# wisleep.net
KiCad netlist of a schematic drawn in EAGLE
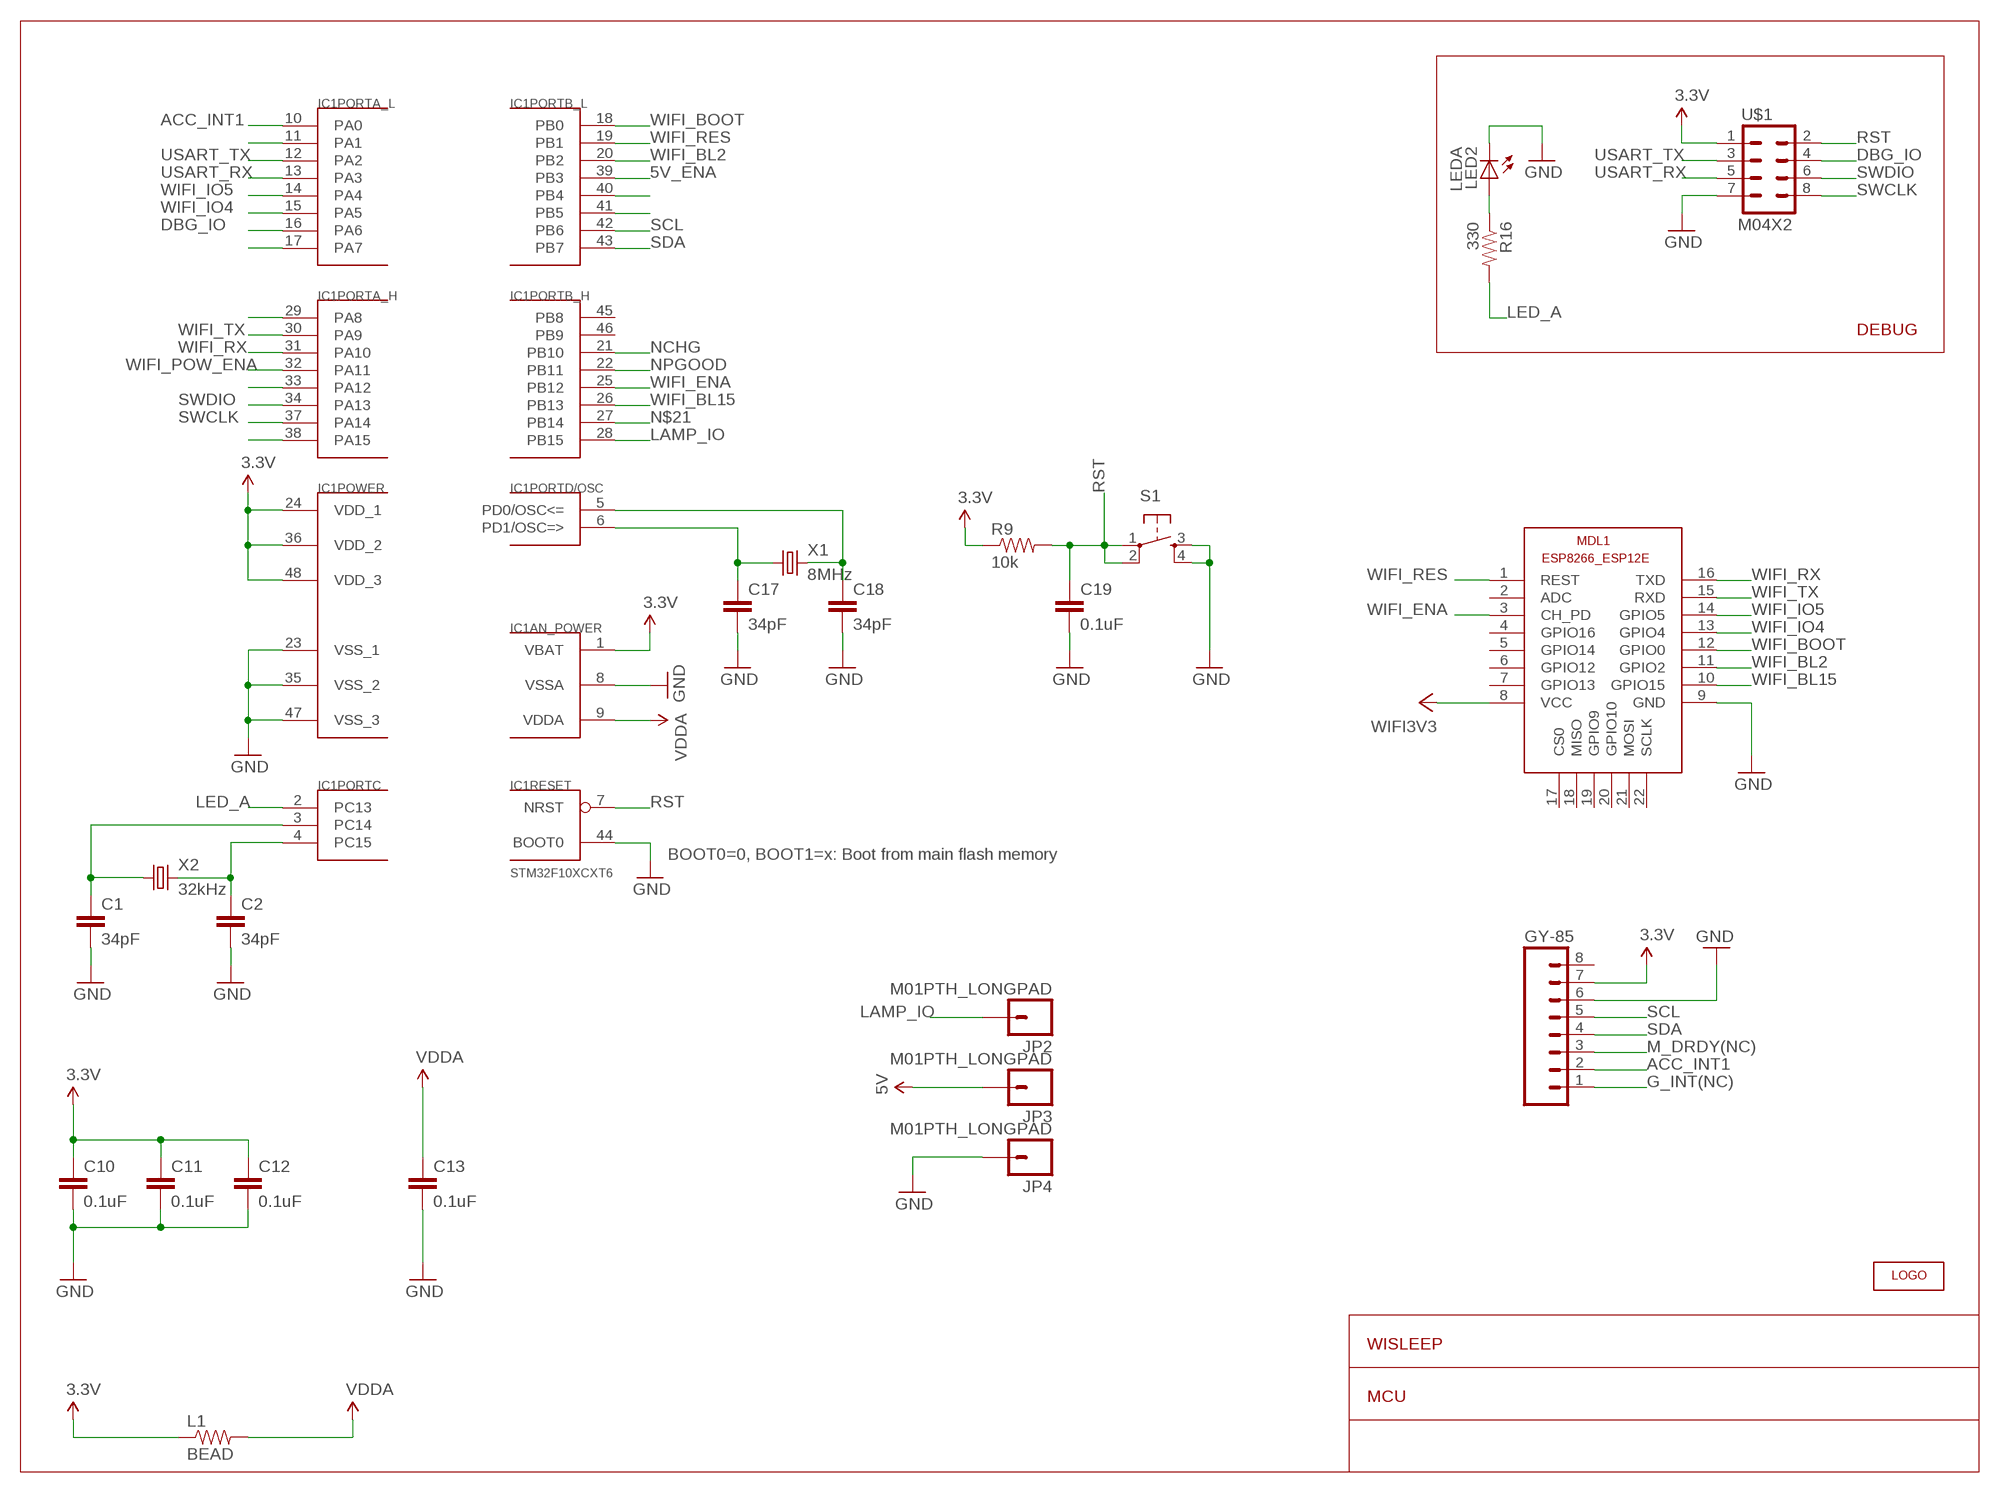
[diagram p0: schematic, sheet 1]
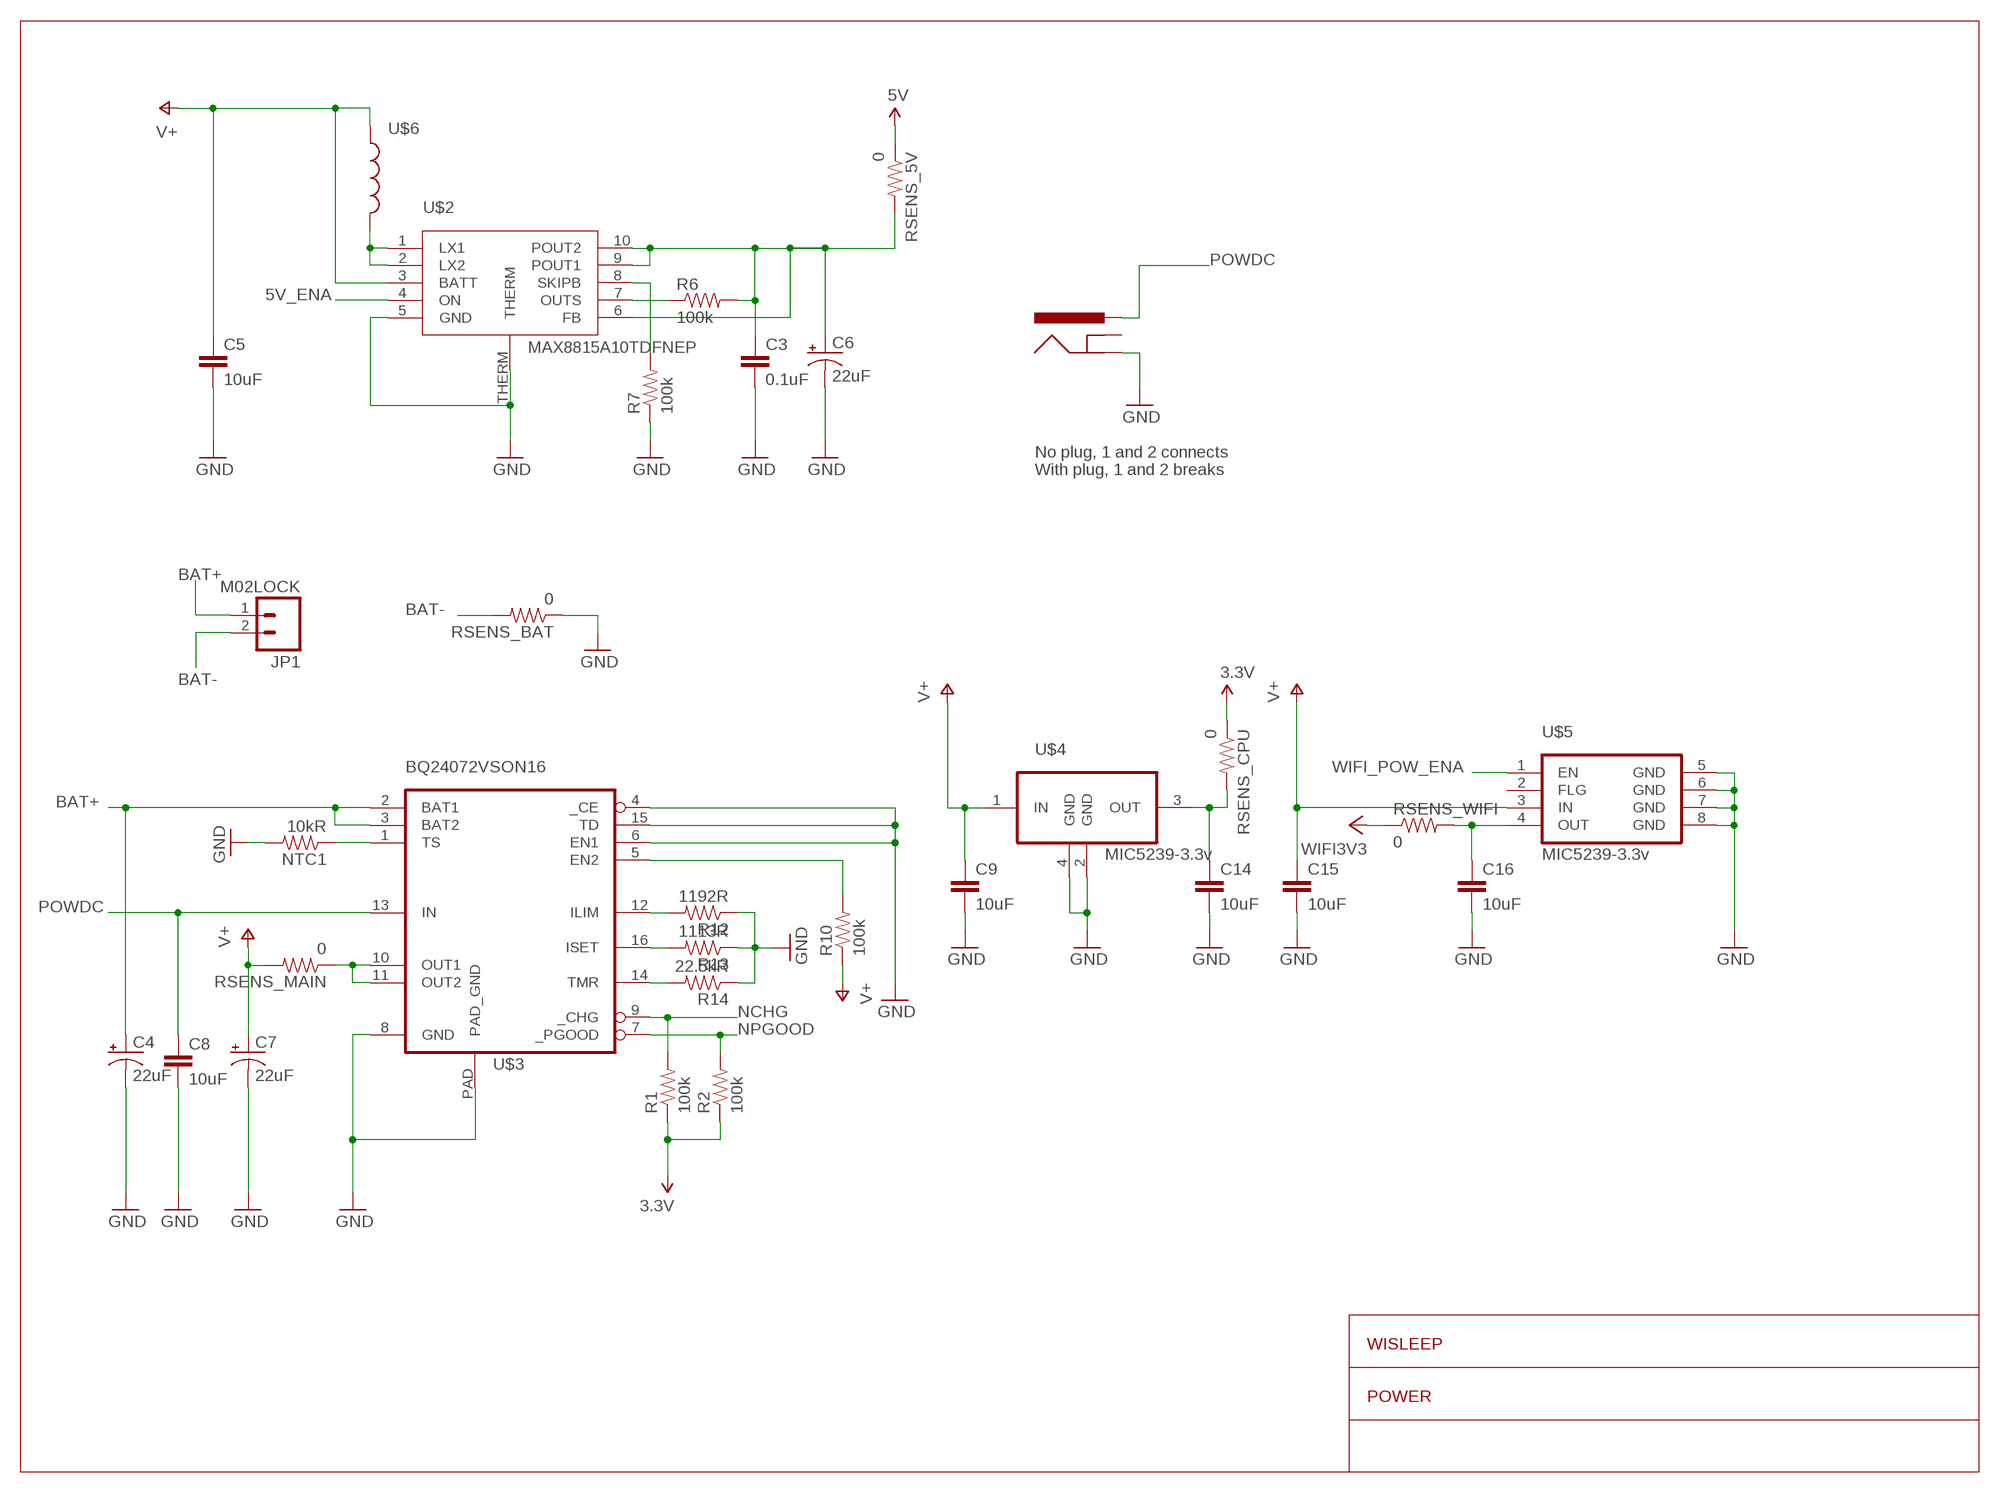
[diagram p1: schematic, sheet 2]

(export (version "E")
  (design (tool "Eeschema 10.0.6"))
  (components
    (comp (ref "C1")
      (value "34pF")
      (footprint "eagle-import:C0402")
      (libsource (lib "eagle-import") (part "CAP0402"))
    )
    (comp (ref "C2")
      (value "34pF")
      (footprint "eagle-import:C0402")
      (libsource (lib "eagle-import") (part "CAP0402"))
    )
    (comp (ref "C10")
      (value "0.1uF")
      (footprint "eagle-import:C0402")
      (libsource (lib "eagle-import") (part "CAP0402"))
    )
    (comp (ref "C11")
      (value "0.1uF")
      (footprint "eagle-import:C0402")
      (libsource (lib "eagle-import") (part "CAP0402"))
    )
    (comp (ref "C12")
      (value "0.1uF")
      (footprint "eagle-import:C0402")
      (libsource (lib "eagle-import") (part "CAP0402"))
    )
    (comp (ref "C13")
      (value "0.1uF")
      (footprint "eagle-import:C0402")
      (libsource (lib "eagle-import") (part "CAP0402"))
    )
    (comp (ref "C17")
      (value "34pF")
      (footprint "eagle-import:C0402")
      (libsource (lib "eagle-import") (part "CAP0402"))
    )
    (comp (ref "C18")
      (value "34pF")
      (footprint "eagle-import:C0402")
      (libsource (lib "eagle-import") (part "CAP0402"))
    )
    (comp (ref "C19")
      (value "0.1uF")
      (footprint "eagle-import:C0402")
      (libsource (lib "eagle-import") (part "CAP0402"))
    )
    (comp (ref "GY-85")
      (value "M08")
      (footprint "eagle-import:1X08")
      (libsource (lib "eagle-import") (part "M08"))
    )
    (comp (ref "IC1")
      (value "STM32F10XCXT6")
      (footprint "eagle-import:TQFP48")
      (libsource (lib "eagle-import") (part "STM32F10XCXT6"))
    )
    (comp (ref "JP2")
      (value "M01PTH_LONGPAD")
      (footprint "eagle-import:1X01_LONGPAD")
      (libsource (lib "eagle-import") (part "M01PTH_LONGPAD"))
    )
    (comp (ref "JP3")
      (value "M01PTH_LONGPAD")
      (footprint "eagle-import:1X01_LONGPAD")
      (libsource (lib "eagle-import") (part "M01PTH_LONGPAD"))
    )
    (comp (ref "JP4")
      (value "M01PTH_LONGPAD")
      (footprint "eagle-import:1X01_LONGPAD")
      (libsource (lib "eagle-import") (part "M01PTH_LONGPAD"))
    )
    (comp (ref "L1")
      (value "BEAD")
      (footprint "eagle-import:0603_GEN")
      (libsource (lib "eagle-import") (part "robot_RESISTOR0603"))
    )
    (comp (ref "LED2")
      (value "LEDA")
      (footprint "eagle-import:LED-0603")
      (libsource (lib "eagle-import") (part "LED0603"))
    )
    (comp (ref "MDL1")
      (value "ESP8266-12EESP8266-ESP12E")
      (footprint "eagle-import:ESP8266-ESP12E")
      (libsource (lib "eagle-import") (part "ESP8266-12EESP8266-ESP12E"))
    )
    (comp (ref "R9")
      (value "10k")
      (footprint "eagle-import:C0402")
      (libsource (lib "eagle-import") (part "RESISTOR0402"))
    )
    (comp (ref "R16")
      (value "330")
      (footprint "eagle-import:C0402")
      (libsource (lib "eagle-import") (part "RESISTOR0402"))
    )
    (comp (ref "S1")
      (value "TAC_SWITCHSMD")
      (footprint "eagle-import:TACTILE_SWITCH_SMD")
      (libsource (lib "eagle-import") (part "TAC_SWITCHSMD"))
    )
    (comp (ref "U$1")
      (value "M04X2")
      (footprint "eagle-import:2X4")
      (libsource (lib "eagle-import") (part "M04X2"))
    )
    (comp (ref "U$7")
      (value "LOGOLOGO")
      (footprint "eagle-import:LOGO")
      (libsource (lib "eagle-import") (part "LOGOLOGO"))
    )
    (comp (ref "X1")
      (value "8MHz")
      (footprint "eagle-import:CRYSTAL_SMD_5X3.2_7A")
      (libsource (lib "eagle-import") (part "CRYSTAL5X3.2_7AOWN"))
    )
    (comp (ref "X2")
      (value "32kHz")
      (footprint "eagle-import:CRYSTAL_SMD_2X0.6")
      (libsource (lib "eagle-import") (part "CRYSTAL"))
    )
    (comp (ref "C3")
      (value "0.1uF")
      (footprint "eagle-import:C0402")
      (libsource (lib "eagle-import") (part "CAP0402"))
    )
    (comp (ref "C4")
      (value "22uF")
      (footprint "eagle-import:EIA3216")
      (libsource (lib "eagle-import") (part "CAP_POL1206_CASE-A"))
    )
    (comp (ref "C5")
      (value "10uF")
      (footprint "eagle-import:C0402")
      (libsource (lib "eagle-import") (part "CAP0402"))
    )
    (comp (ref "C6")
      (value "22uF")
      (footprint "eagle-import:EIA3216")
      (libsource (lib "eagle-import") (part "CAP_POL1206_CASE-A"))
    )
    (comp (ref "C7")
      (value "22uF")
      (footprint "eagle-import:EIA3216")
      (libsource (lib "eagle-import") (part "CAP_POL1206_CASE-A"))
    )
    (comp (ref "C8")
      (value "10uF")
      (footprint "eagle-import:C0402")
      (libsource (lib "eagle-import") (part "CAP0402"))
    )
    (comp (ref "C9")
      (value "10uF")
      (footprint "eagle-import:C0402")
      (libsource (lib "eagle-import") (part "CAP0402"))
    )
    (comp (ref "C14")
      (value "10uF")
      (footprint "eagle-import:C0402")
      (libsource (lib "eagle-import") (part "CAP0402"))
    )
    (comp (ref "C15")
      (value "10uF")
      (footprint "eagle-import:C0402")
      (libsource (lib "eagle-import") (part "CAP0402"))
    )
    (comp (ref "C16")
      (value "10uF")
      (footprint "eagle-import:C0402")
      (libsource (lib "eagle-import") (part "CAP0402"))
    )
    (comp (ref "JP1")
      (value "M02LOCK")
      (footprint "eagle-import:1X02_LOCK")
      (libsource (lib "eagle-import") (part "M02LOCK"))
    )
    (comp (ref "NTC1")
      (value "10kR")
      (footprint "eagle-import:C0402")
      (libsource (lib "eagle-import") (part "RESISTOR0402"))
    )
    (comp (ref "R1")
      (value "100k")
      (footprint "eagle-import:C0402")
      (libsource (lib "eagle-import") (part "RESISTOR0402"))
    )
    (comp (ref "R2")
      (value "100k")
      (footprint "eagle-import:C0402")
      (libsource (lib "eagle-import") (part "RESISTOR0402"))
    )
    (comp (ref "R6")
      (value "100k")
      (footprint "eagle-import:C0402")
      (libsource (lib "eagle-import") (part "RESISTOR0402"))
    )
    (comp (ref "R7")
      (value "100k")
      (footprint "eagle-import:C0402")
      (libsource (lib "eagle-import") (part "RESISTOR0402"))
    )
    (comp (ref "R10")
      (value "100k")
      (footprint "eagle-import:C0402")
      (libsource (lib "eagle-import") (part "RESISTOR0402"))
    )
    (comp (ref "R12")
      (value "1192R")
      (footprint "eagle-import:C0402")
      (libsource (lib "eagle-import") (part "RESISTOR0402"))
    )
    (comp (ref "R13")
      (value "1113R")
      (footprint "eagle-import:C0402")
      (libsource (lib "eagle-import") (part "RESISTOR0402"))
    )
    (comp (ref "R14")
      (value "22.5kR")
      (footprint "eagle-import:C0402")
      (libsource (lib "eagle-import") (part "RESISTOR0402"))
    )
    (comp (ref "RSENS_5V")
      (value "0")
      (footprint "eagle-import:C0402")
      (libsource (lib "eagle-import") (part "RESISTOR0402"))
    )
    (comp (ref "RSENS_BAT")
      (value "0")
      (footprint "eagle-import:C0402")
      (libsource (lib "eagle-import") (part "RESISTOR0402"))
    )
    (comp (ref "RSENS_CPU")
      (value "0")
      (footprint "eagle-import:C0402")
      (libsource (lib "eagle-import") (part "RESISTOR0402"))
    )
    (comp (ref "RSENS_MAIN")
      (value "0")
      (footprint "eagle-import:C0402")
      (libsource (lib "eagle-import") (part "RESISTOR0402"))
    )
    (comp (ref "RSENS_WIFI")
      (value "0")
      (footprint "eagle-import:C0402")
      (libsource (lib "eagle-import") (part "RESISTOR0402"))
    )
    (comp (ref "U$2")
      (value "MAX8815A10TDFNEP")
      (footprint "eagle-import:10-TDFN-EP")
      (libsource (lib "eagle-import") (part "MAX8815A10TDFNEP"))
    )
    (comp (ref "U$3")
      (value "BQ24072VSON16")
      (footprint "eagle-import:VSON16")
      (libsource (lib "eagle-import") (part "BQ24072VSON16"))
    )
    (comp (ref "U$4")
      (value "MIC5239-3.3v")
      (footprint "eagle-import:SOT223")
      (libsource (lib "eagle-import") (part "MIC5239SOT223SOT223"))
    )
    (comp (ref "U$5")
      (value "MIC5239-3.3v")
      (footprint "eagle-import:MSOP08")
      (libsource (lib "eagle-import") (part "MIC5239-8MSOP"))
    )
    (comp (ref "U$6")
      (value "INDUCTOR3014")
      (footprint "eagle-import:INDUCTOR-3014")
      (libsource (lib "eagle-import") (part "INDUCTOR3014"))
    )
    (comp (ref "U$8")
      (value "POWER_JACKPTH")
      (footprint "eagle-import:POWER_JACK_PTH")
      (libsource (lib "eagle-import") (part "POWER_JACKPTH"))
    )
  )
  (nets
    (net (code "1") (name "3.3V") (class "Default")
      (node (ref "C10") (pin "1") (pinfunction "1_1") (pintype "passive"))
      (node (ref "C11") (pin "1") (pinfunction "1_1") (pintype "passive"))
      (node (ref "C12") (pin "1") (pinfunction "1_1") (pintype "passive"))
      (node (ref "GY-85") (pin "7") (pinfunction "7_7") (pintype "passive"))
      (node (ref "IC1") (pin "1") (pinfunction "VBAT_1") (pintype "power_in"))
      (node (ref "IC1") (pin "24") (pinfunction "VDD_1_24") (pintype "power_in"))
      (node (ref "IC1") (pin "36") (pinfunction "VDD_2_36") (pintype "power_in"))
      (node (ref "IC1") (pin "48") (pinfunction "VDD_3_48") (pintype "power_in"))
      (node (ref "L1") (pin "1") (pinfunction "1_1") (pintype "passive"))
      (node (ref "R1") (pin "1") (pinfunction "1_1") (pintype "passive"))
      (node (ref "R2") (pin "1") (pinfunction "1_1") (pintype "passive"))
      (node (ref "R9") (pin "1") (pinfunction "1_1") (pintype "passive"))
      (node (ref "RSENS_CPU") (pin "1") (pinfunction "1_1") (pintype "passive"))
      (node (ref "U$1") (pin "1") (pinfunction "1_1") (pintype "passive"))
    )
    (net (code "2") (name "5V") (class "Default")
      (node (ref "JP3") (pin "1") (pinfunction "1_1") (pintype "passive"))
      (node (ref "RSENS_5V") (pin "1") (pinfunction "1_1") (pintype "passive"))
    )
    (net (code "3") (name "5V_ENA") (class "Default")
      (node (ref "IC1") (pin "39") (pinfunction "PB3_39") (pintype "bidirectional"))
      (node (ref "U$2") (pin "4") (pinfunction "ON_4") (pintype "input"))
    )
    (net (code "4") (name "ACC_INT1") (class "Default")
      (node (ref "GY-85") (pin "2") (pinfunction "2_2") (pintype "passive"))
      (node (ref "IC1") (pin "10") (pinfunction "PA0_10") (pintype "bidirectional"))
    )
    (net (code "5") (name "BAT+") (class "Default")
      (node (ref "C4") (pin "A") (pinfunction "+_A") (pintype "passive"))
      (node (ref "JP1") (pin "1") (pinfunction "1_1") (pintype "passive"))
      (node (ref "U$3") (pin "2") (pinfunction "BAT1_2") (pintype "power_in"))
      (node (ref "U$3") (pin "3") (pinfunction "BAT2_3") (pintype "power_in"))
    )
    (net (code "6") (name "BAT-") (class "Default")
      (node (ref "JP1") (pin "2") (pinfunction "2_2") (pintype "passive"))
      (node (ref "RSENS_BAT") (pin "2") (pinfunction "2_2") (pintype "passive"))
    )
    (net (code "7") (name "DBG_IO") (class "Default")
      (node (ref "IC1") (pin "16") (pinfunction "PA6_16") (pintype "bidirectional"))
      (node (ref "U$1") (pin "4") (pinfunction "4_4") (pintype "passive"))
    )
    (net (code "8") (name "GND") (class "Default")
      (node (ref "C1") (pin "2") (pinfunction "2_2") (pintype "passive"))
      (node (ref "C10") (pin "2") (pinfunction "2_2") (pintype "passive"))
      (node (ref "C11") (pin "2") (pinfunction "2_2") (pintype "passive"))
      (node (ref "C12") (pin "2") (pinfunction "2_2") (pintype "passive"))
      (node (ref "C13") (pin "2") (pinfunction "2_2") (pintype "passive"))
      (node (ref "C14") (pin "2") (pinfunction "2_2") (pintype "passive"))
      (node (ref "C15") (pin "2") (pinfunction "2_2") (pintype "passive"))
      (node (ref "C16") (pin "2") (pinfunction "2_2") (pintype "passive"))
      (node (ref "C17") (pin "2") (pinfunction "2_2") (pintype "passive"))
      (node (ref "C18") (pin "2") (pinfunction "2_2") (pintype "passive"))
      (node (ref "C19") (pin "2") (pinfunction "2_2") (pintype "passive"))
      (node (ref "C2") (pin "2") (pinfunction "2_2") (pintype "passive"))
      (node (ref "C3") (pin "2") (pinfunction "2_2") (pintype "passive"))
      (node (ref "C4") (pin "C") (pinfunction "-_C") (pintype "passive"))
      (node (ref "C5") (pin "2") (pinfunction "2_2") (pintype "passive"))
      (node (ref "C6") (pin "C") (pinfunction "-_C") (pintype "passive"))
      (node (ref "C7") (pin "C") (pinfunction "-_C") (pintype "passive"))
      (node (ref "C8") (pin "2") (pinfunction "2_2") (pintype "passive"))
      (node (ref "C9") (pin "2") (pinfunction "2_2") (pintype "passive"))
      (node (ref "GY-85") (pin "6") (pinfunction "6_6") (pintype "passive"))
      (node (ref "IC1") (pin "23") (pinfunction "VSS_1_23") (pintype "power_in"))
      (node (ref "IC1") (pin "35") (pinfunction "VSS_2_35") (pintype "power_in"))
      (node (ref "IC1") (pin "44") (pinfunction "BOOT0_44") (pintype "input"))
      (node (ref "IC1") (pin "47") (pinfunction "VSS_3_47") (pintype "power_in"))
      (node (ref "IC1") (pin "8") (pinfunction "VSSA_8") (pintype "power_in"))
      (node (ref "JP4") (pin "1") (pinfunction "1_1") (pintype "passive"))
      (node (ref "LED2") (pin "C") (pinfunction "C_C") (pintype "passive"))
      (node (ref "MDL1") (pin "9") (pinfunction "GND_9") (pintype "bidirectional"))
      (node (ref "NTC1") (pin "2") (pinfunction "2_2") (pintype "passive"))
      (node (ref "R12") (pin "1") (pinfunction "1_1") (pintype "passive"))
      (node (ref "R13") (pin "1") (pinfunction "1_1") (pintype "passive"))
      (node (ref "R14") (pin "1") (pinfunction "1_1") (pintype "passive"))
      (node (ref "R7") (pin "1") (pinfunction "1_1") (pintype "passive"))
      (node (ref "RSENS_BAT") (pin "1") (pinfunction "1_1") (pintype "passive"))
      (node (ref "S1") (pin "3") (pinfunction "3_3") (pintype "passive"))
      (node (ref "S1") (pin "4") (pinfunction "4_4") (pintype "passive"))
      (node (ref "U$1") (pin "7") (pinfunction "7_7") (pintype "passive"))
      (node (ref "U$2") (pin "5") (pinfunction "GND_5") (pintype "power_in"))
      (node (ref "U$2") (pin "THERM") (pinfunction "THERM_THERM") (pintype "power_in"))
      (node (ref "U$3") (pin "15") (pinfunction "TD_15") (pintype "input"))
      (node (ref "U$3") (pin "4") (pinfunction "_CE_4") (pintype "input"))
      (node (ref "U$3") (pin "6") (pinfunction "EN1_6") (pintype "input"))
      (node (ref "U$3") (pin "8") (pinfunction "GND_8") (pintype "power_in"))
      (node (ref "U$3") (pin "PAD") (pinfunction "PAD_GND_PAD") (pintype "power_in"))
      (node (ref "U$4") (pin "2") (pinfunction "GND_2") (pintype "power_in"))
      (node (ref "U$4") (pin "4") (pinfunction "GND_4") (pintype "power_in"))
      (node (ref "U$5") (pin "5") (pinfunction "GND_5") (pintype "power_in"))
      (node (ref "U$5") (pin "6") (pinfunction "GND_6") (pintype "power_in"))
      (node (ref "U$5") (pin "7") (pinfunction "GND_7") (pintype "power_in"))
      (node (ref "U$5") (pin "8") (pinfunction "GND_8") (pintype "power_in"))
      (node (ref "U$8") (pin "GND") (pinfunction "GND_GND") (pintype "bidirectional"))
    )
    (net (code "9") (name "G_INT(NC)") (class "Default")
      (node (ref "GY-85") (pin "1") (pinfunction "1_1") (pintype "passive"))
    )
    (net (code "10") (name "LAMP_IO") (class "Default")
      (node (ref "IC1") (pin "28") (pinfunction "PB15_28") (pintype "bidirectional"))
      (node (ref "JP2") (pin "1") (pinfunction "1_1") (pintype "passive"))
    )
    (net (code "11") (name "LED_A") (class "Default")
      (node (ref "IC1") (pin "2") (pinfunction "PC13_2") (pintype "bidirectional"))
      (node (ref "R16") (pin "2") (pinfunction "2_2") (pintype "passive"))
    )
    (net (code "12") (name "M_DRDY(NC)") (class "Default")
      (node (ref "GY-85") (pin "3") (pinfunction "3_3") (pintype "passive"))
    )
    (net (code "13") (name "N$21") (class "Default")
      (node (ref "IC1") (pin "27") (pinfunction "PB14_27") (pintype "bidirectional"))
    )
    (net (code "14") (name "NCHG") (class "Default")
      (node (ref "IC1") (pin "21") (pinfunction "PB10_21") (pintype "bidirectional"))
      (node (ref "R1") (pin "2") (pinfunction "2_2") (pintype "passive"))
      (node (ref "U$3") (pin "9") (pinfunction "_CHG_9") (pintype "output"))
    )
    (net (code "15") (name "NPGOOD") (class "Default")
      (node (ref "IC1") (pin "22") (pinfunction "PB11_22") (pintype "bidirectional"))
      (node (ref "R2") (pin "2") (pinfunction "2_2") (pintype "passive"))
      (node (ref "U$3") (pin "7") (pinfunction "_PGOOD_7") (pintype "output"))
    )
    (net (code "16") (name "Net-(C6-+)") (class "Default")
      (node (ref "C3") (pin "1") (pinfunction "1_1") (pintype "passive"))
      (node (ref "C6") (pin "A") (pinfunction "+_A") (pintype "passive"))
      (node (ref "R6") (pin "2") (pinfunction "2_2") (pintype "passive"))
      (node (ref "RSENS_5V") (pin "2") (pinfunction "2_2") (pintype "passive"))
      (node (ref "U$2") (pin "10") (pinfunction "POUT2_10") (pintype "power_in"))
      (node (ref "U$2") (pin "6") (pinfunction "FB_6") (pintype "input"))
      (node (ref "U$2") (pin "9") (pinfunction "POUT1_9") (pintype "power_in"))
    )
    (net (code "17") (name "Net-(IC1F-PC14)") (class "Default")
      (node (ref "C1") (pin "1") (pinfunction "1_1") (pintype "passive"))
      (node (ref "IC1") (pin "3") (pinfunction "PC14_3") (pintype "bidirectional"))
      (node (ref "X2") (pin "P$1") (pinfunction "1_P$1") (pintype "passive"))
    )
    (net (code "18") (name "Net-(IC1F-PC15)") (class "Default")
      (node (ref "C2") (pin "1") (pinfunction "1_1") (pintype "passive"))
      (node (ref "IC1") (pin "4") (pinfunction "PC15_4") (pintype "bidirectional"))
      (node (ref "X2") (pin "P$2") (pinfunction "2_P$2") (pintype "passive"))
    )
    (net (code "19") (name "Net-(IC1G-PD0{slash}OSC<=)") (class "Default")
      (node (ref "C18") (pin "1") (pinfunction "1_1") (pintype "passive"))
      (node (ref "IC1") (pin "5") (pinfunction "PD0/OSC<=_5") (pintype "bidirectional"))
      (node (ref "X1") (pin "P$2") (pinfunction "2_P$2") (pintype "passive"))
    )
    (net (code "20") (name "Net-(IC1G-PD1{slash}OSC=>)") (class "Default")
      (node (ref "C17") (pin "1") (pinfunction "1_1") (pintype "passive"))
      (node (ref "IC1") (pin "6") (pinfunction "PD1/OSC=>_6") (pintype "bidirectional"))
      (node (ref "X1") (pin "P$1") (pinfunction "1_P$1") (pintype "passive"))
    )
    (net (code "21") (name "Net-(LED2-PadA)") (class "Default")
      (node (ref "LED2") (pin "A") (pinfunction "A_A") (pintype "passive"))
      (node (ref "R16") (pin "1") (pinfunction "1_1") (pintype "passive"))
    )
    (net (code "22") (name "Net-(U$2-LX1)") (class "Default")
      (node (ref "U$2") (pin "1") (pinfunction "LX1_1") (pintype "bidirectional"))
      (node (ref "U$2") (pin "2") (pinfunction "LX2_2") (pintype "bidirectional"))
      (node (ref "U$6") (pin "P$2") (pinfunction "2_P$2") (pintype "passive"))
    )
    (net (code "23") (name "Net-(U$2-OUTS)") (class "Default")
      (node (ref "R6") (pin "1") (pinfunction "1_1") (pintype "passive"))
      (node (ref "U$2") (pin "7") (pinfunction "OUTS_7") (pintype "bidirectional"))
    )
    (net (code "24") (name "Net-(U$2-SKIPB)") (class "Default")
      (node (ref "R7") (pin "2") (pinfunction "2_2") (pintype "passive"))
      (node (ref "U$2") (pin "8") (pinfunction "SKIPB_8") (pintype "input"))
    )
    (net (code "25") (name "Net-(U$3-EN2)") (class "Default")
      (node (ref "R10") (pin "2") (pinfunction "2_2") (pintype "passive"))
      (node (ref "U$3") (pin "5") (pinfunction "EN2_5") (pintype "input"))
    )
    (net (code "26") (name "Net-(U$3-ILIM)") (class "Default")
      (node (ref "R12") (pin "2") (pinfunction "2_2") (pintype "passive"))
      (node (ref "U$3") (pin "12") (pinfunction "ILIM_12") (pintype "input"))
    )
    (net (code "27") (name "Net-(U$3-ISET)") (class "Default")
      (node (ref "R13") (pin "2") (pinfunction "2_2") (pintype "passive"))
      (node (ref "U$3") (pin "16") (pinfunction "ISET_16") (pintype "input"))
    )
    (net (code "28") (name "Net-(U$3-OUT1)") (class "Default")
      (node (ref "RSENS_MAIN") (pin "1") (pinfunction "1_1") (pintype "passive"))
      (node (ref "U$3") (pin "10") (pinfunction "OUT1_10") (pintype "power_in"))
      (node (ref "U$3") (pin "11") (pinfunction "OUT2_11") (pintype "power_in"))
    )
    (net (code "29") (name "Net-(U$3-TMR)") (class "Default")
      (node (ref "R14") (pin "2") (pinfunction "2_2") (pintype "passive"))
      (node (ref "U$3") (pin "14") (pinfunction "TMR_14") (pintype "input"))
    )
    (net (code "30") (name "Net-(U$3-TS)") (class "Default")
      (node (ref "NTC1") (pin "1") (pinfunction "1_1") (pintype "passive"))
      (node (ref "U$3") (pin "1") (pinfunction "TS_1") (pintype "bidirectional"))
    )
    (net (code "31") (name "Net-(U$4-OUT)") (class "Default")
      (node (ref "C14") (pin "1") (pinfunction "1_1") (pintype "passive"))
      (node (ref "RSENS_CPU") (pin "2") (pinfunction "2_2") (pintype "passive"))
      (node (ref "U$4") (pin "3") (pinfunction "OUT_3") (pintype "power_in"))
    )
    (net (code "32") (name "Net-(U$5-OUT)") (class "Default")
      (node (ref "C16") (pin "1") (pinfunction "1_1") (pintype "passive"))
      (node (ref "RSENS_WIFI") (pin "2") (pinfunction "2_2") (pintype "passive"))
      (node (ref "U$5") (pin "4") (pinfunction "OUT_4") (pintype "power_in"))
    )
    (net (code "33") (name "POWDC") (class "Default")
      (node (ref "C8") (pin "1") (pinfunction "1_1") (pintype "passive"))
      (node (ref "U$3") (pin "13") (pinfunction "IN_13") (pintype "power_in"))
      (node (ref "U$8") (pin "PWR") (pinfunction "PWR_PWR") (pintype "bidirectional"))
    )
    (net (code "34") (name "RST") (class "Default")
      (node (ref "C19") (pin "1") (pinfunction "1_1") (pintype "passive"))
      (node (ref "IC1") (pin "7") (pinfunction "NRST_7") (pintype "input"))
      (node (ref "R9") (pin "2") (pinfunction "2_2") (pintype "passive"))
      (node (ref "S1") (pin "1") (pinfunction "1_1") (pintype "passive"))
      (node (ref "S1") (pin "2") (pinfunction "2_2") (pintype "passive"))
      (node (ref "U$1") (pin "2") (pinfunction "2_2") (pintype "passive"))
    )
    (net (code "35") (name "SCL") (class "Default")
      (node (ref "GY-85") (pin "5") (pinfunction "5_5") (pintype "passive"))
      (node (ref "IC1") (pin "42") (pinfunction "PB6_42") (pintype "bidirectional"))
    )
    (net (code "36") (name "SDA") (class "Default")
      (node (ref "GY-85") (pin "4") (pinfunction "4_4") (pintype "passive"))
      (node (ref "IC1") (pin "43") (pinfunction "PB7_43") (pintype "bidirectional"))
    )
    (net (code "37") (name "SWCLK") (class "Default")
      (node (ref "IC1") (pin "37") (pinfunction "PA14_37") (pintype "bidirectional"))
      (node (ref "U$1") (pin "8") (pinfunction "8_8") (pintype "passive"))
    )
    (net (code "38") (name "SWDIO") (class "Default")
      (node (ref "IC1") (pin "34") (pinfunction "PA13_34") (pintype "bidirectional"))
      (node (ref "U$1") (pin "6") (pinfunction "6_6") (pintype "passive"))
    )
    (net (code "39") (name "USART_RX") (class "Default")
      (node (ref "IC1") (pin "13") (pinfunction "PA3_13") (pintype "bidirectional"))
      (node (ref "U$1") (pin "5") (pinfunction "5_5") (pintype "passive"))
    )
    (net (code "40") (name "USART_TX") (class "Default")
      (node (ref "IC1") (pin "12") (pinfunction "PA2_12") (pintype "bidirectional"))
      (node (ref "U$1") (pin "3") (pinfunction "3_3") (pintype "passive"))
    )
    (net (code "41") (name "V+") (class "Default")
      (node (ref "C15") (pin "1") (pinfunction "1_1") (pintype "passive"))
      (node (ref "C5") (pin "1") (pinfunction "1_1") (pintype "passive"))
      (node (ref "C7") (pin "A") (pinfunction "+_A") (pintype "passive"))
      (node (ref "C9") (pin "1") (pinfunction "1_1") (pintype "passive"))
      (node (ref "R10") (pin "1") (pinfunction "1_1") (pintype "passive"))
      (node (ref "RSENS_MAIN") (pin "2") (pinfunction "2_2") (pintype "passive"))
      (node (ref "U$2") (pin "3") (pinfunction "BATT_3") (pintype "power_in"))
      (node (ref "U$4") (pin "1") (pinfunction "IN_1") (pintype "power_in"))
      (node (ref "U$5") (pin "3") (pinfunction "IN_3") (pintype "power_in"))
      (node (ref "U$6") (pin "P$1") (pinfunction "1_P$1") (pintype "passive"))
    )
    (net (code "42") (name "VCC") (class "Default")
      (node (ref "MDL1") (pin "8") (pinfunction "VCC_8") (pintype "bidirectional"))
      (node (ref "RSENS_WIFI") (pin "1") (pinfunction "1_1") (pintype "passive"))
    )
    (net (code "43") (name "VDDA") (class "Default")
      (node (ref "C13") (pin "1") (pinfunction "1_1") (pintype "passive"))
      (node (ref "IC1") (pin "9") (pinfunction "VDDA_9") (pintype "power_in"))
      (node (ref "L1") (pin "2") (pinfunction "2_2") (pintype "passive"))
    )
    (net (code "44") (name "WIFI_BL2") (class "Default")
      (node (ref "IC1") (pin "20") (pinfunction "PB2_20") (pintype "bidirectional"))
      (node (ref "MDL1") (pin "11") (pinfunction "GPIO2_11") (pintype "bidirectional"))
    )
    (net (code "45") (name "WIFI_BL15") (class "Default")
      (node (ref "IC1") (pin "26") (pinfunction "PB13_26") (pintype "bidirectional"))
      (node (ref "MDL1") (pin "10") (pinfunction "GPIO15_10") (pintype "bidirectional"))
    )
    (net (code "46") (name "WIFI_BOOT") (class "Default")
      (node (ref "IC1") (pin "18") (pinfunction "PB0_18") (pintype "bidirectional"))
      (node (ref "MDL1") (pin "12") (pinfunction "GPIO0_12") (pintype "bidirectional"))
    )
    (net (code "47") (name "WIFI_ENA") (class "Default")
      (node (ref "IC1") (pin "25") (pinfunction "PB12_25") (pintype "bidirectional"))
      (node (ref "MDL1") (pin "3") (pinfunction "CH_PD_3") (pintype "bidirectional"))
    )
    (net (code "48") (name "WIFI_IO4") (class "Default")
      (node (ref "IC1") (pin "15") (pinfunction "PA5_15") (pintype "bidirectional"))
      (node (ref "MDL1") (pin "13") (pinfunction "GPIO4_13") (pintype "bidirectional"))
    )
    (net (code "49") (name "WIFI_IO5") (class "Default")
      (node (ref "IC1") (pin "14") (pinfunction "PA4_14") (pintype "bidirectional"))
      (node (ref "MDL1") (pin "14") (pinfunction "GPIO5_14") (pintype "bidirectional"))
    )
    (net (code "50") (name "WIFI_POW_ENA") (class "Default")
      (node (ref "IC1") (pin "32") (pinfunction "PA11_32") (pintype "bidirectional"))
      (node (ref "U$5") (pin "1") (pinfunction "EN_1") (pintype "input"))
    )
    (net (code "51") (name "WIFI_RES") (class "Default")
      (node (ref "IC1") (pin "19") (pinfunction "PB1_19") (pintype "bidirectional"))
      (node (ref "MDL1") (pin "1") (pinfunction "REST_1") (pintype "bidirectional"))
    )
    (net (code "52") (name "WIFI_RX") (class "Default")
      (node (ref "IC1") (pin "31") (pinfunction "PA10_31") (pintype "bidirectional"))
      (node (ref "MDL1") (pin "16") (pinfunction "TXD_16") (pintype "bidirectional"))
    )
    (net (code "53") (name "WIFI_TX") (class "Default")
      (node (ref "IC1") (pin "30") (pinfunction "PA9_30") (pintype "bidirectional"))
      (node (ref "MDL1") (pin "15") (pinfunction "RXD_15") (pintype "bidirectional"))
    )
    (net (code "54") (name "unconnected-(GY-85-Pad8)") (class "Default")
      (node (ref "GY-85") (pin "8") (pinfunction "8_8") (pintype "passive"))
    )
    (net (code "55") (name "unconnected-(IC1B-PA8-Pad29)") (class "Default")
      (node (ref "IC1") (pin "29") (pinfunction "PA8_29") (pintype "bidirectional"))
    )
    (net (code "56") (name "unconnected-(IC1B-PA12-Pad33)") (class "Default")
      (node (ref "IC1") (pin "33") (pinfunction "PA12_33") (pintype "bidirectional"))
    )
    (net (code "57") (name "unconnected-(IC1B-PA15-Pad38)") (class "Default")
      (node (ref "IC1") (pin "38") (pinfunction "PA15_38") (pintype "bidirectional"))
    )
    (net (code "58") (name "unconnected-(IC1C-PA1-Pad11)") (class "Default")
      (node (ref "IC1") (pin "11") (pinfunction "PA1_11") (pintype "bidirectional"))
    )
    (net (code "59") (name "unconnected-(IC1C-PA7-Pad17)") (class "Default")
      (node (ref "IC1") (pin "17") (pinfunction "PA7_17") (pintype "bidirectional"))
    )
    (net (code "60") (name "unconnected-(IC1D-PB8-Pad45)") (class "Default")
      (node (ref "IC1") (pin "45") (pinfunction "PB8_45") (pintype "bidirectional"))
    )
    (net (code "61") (name "unconnected-(IC1D-PB9-Pad46)") (class "Default")
      (node (ref "IC1") (pin "46") (pinfunction "PB9_46") (pintype "bidirectional"))
    )
    (net (code "62") (name "unconnected-(IC1E-PB4-Pad40)") (class "Default")
      (node (ref "IC1") (pin "40") (pinfunction "PB4_40") (pintype "bidirectional"))
    )
    (net (code "63") (name "unconnected-(IC1E-PB5-Pad41)") (class "Default")
      (node (ref "IC1") (pin "41") (pinfunction "PB5_41") (pintype "bidirectional"))
    )
    (net (code "64") (name "unconnected-(MDL1-ADC-Pad2)") (class "Default")
      (node (ref "MDL1") (pin "2") (pinfunction "ADC_2") (pintype "bidirectional"))
    )
    (net (code "65") (name "unconnected-(MDL1-CS0-Pad17)") (class "Default")
      (node (ref "MDL1") (pin "17") (pinfunction "CS0_17") (pintype "bidirectional"))
    )
    (net (code "66") (name "unconnected-(MDL1-GPIO9-Pad19)") (class "Default")
      (node (ref "MDL1") (pin "19") (pinfunction "GPIO9_19") (pintype "bidirectional"))
    )
    (net (code "67") (name "unconnected-(MDL1-GPIO10-Pad20)") (class "Default")
      (node (ref "MDL1") (pin "20") (pinfunction "GPIO10_20") (pintype "bidirectional"))
    )
    (net (code "68") (name "unconnected-(MDL1-GPIO12-Pad6)") (class "Default")
      (node (ref "MDL1") (pin "6") (pinfunction "GPIO12_6") (pintype "bidirectional"))
    )
    (net (code "69") (name "unconnected-(MDL1-GPIO13-Pad7)") (class "Default")
      (node (ref "MDL1") (pin "7") (pinfunction "GPIO13_7") (pintype "bidirectional"))
    )
    (net (code "70") (name "unconnected-(MDL1-GPIO14-Pad5)") (class "Default")
      (node (ref "MDL1") (pin "5") (pinfunction "GPIO14_5") (pintype "bidirectional"))
    )
    (net (code "71") (name "unconnected-(MDL1-GPIO16-Pad4)") (class "Default")
      (node (ref "MDL1") (pin "4") (pinfunction "GPIO16_4") (pintype "bidirectional"))
    )
    (net (code "72") (name "unconnected-(MDL1-MISO-Pad18)") (class "Default")
      (node (ref "MDL1") (pin "18") (pinfunction "MISO_18") (pintype "bidirectional"))
    )
    (net (code "73") (name "unconnected-(MDL1-MOSI-Pad21)") (class "Default")
      (node (ref "MDL1") (pin "21") (pinfunction "MOSI_21") (pintype "bidirectional"))
    )
    (net (code "74") (name "unconnected-(MDL1-SCLK-Pad22)") (class "Default")
      (node (ref "MDL1") (pin "22") (pinfunction "SCLK_22") (pintype "bidirectional"))
    )
    (net (code "75") (name "unconnected-(U$5-FLG-Pad2)") (class "Default")
      (node (ref "U$5") (pin "2") (pinfunction "FLG_2") (pintype "output"))
    )
    (net (code "76") (name "unconnected-(U$8-PadGNDBREAK)") (class "Default")
      (node (ref "U$8") (pin "GNDBREAK") (pinfunction "GNDBREAK_GNDBREAK") (pintype "bidirectional"))
    )
  )
)
